# AVR-Megaboard-V1.net
KiCad netlist of a schematic drawn in EAGLE
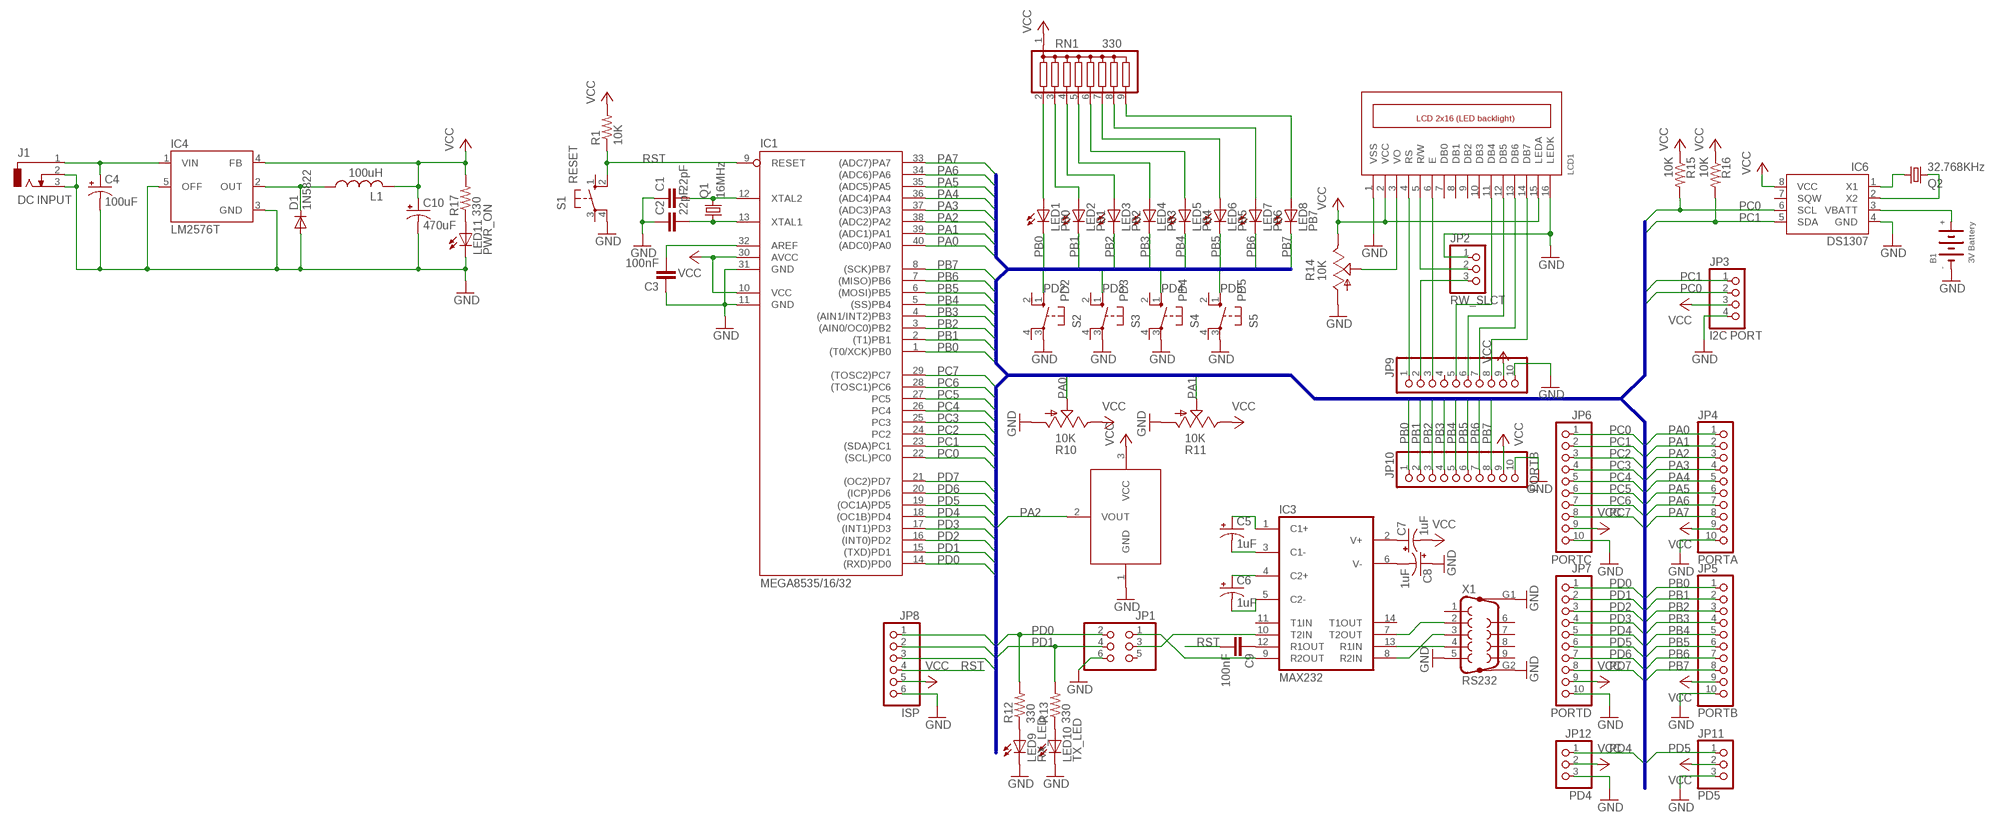
[diagram p0: schematic, sheet 1]

(export (version "E")
  (design (tool "Eeschema 10.0.6"))
  (components
    (comp (ref "B1")
      (value "3V Battery")
      (footprint "eagle-import:CR2032")
      (libsource (lib "eagle-import") (part "BATTERYCR2032"))
    )
    (comp (ref "C1")
      (value "22pF")
      (footprint "eagle-import:C025-024X044")
      (libsource (lib "eagle-import") (part "C-EU025-024X044"))
    )
    (comp (ref "C2")
      (value "22pF")
      (footprint "eagle-import:C025-024X044")
      (libsource (lib "eagle-import") (part "C-EU025-024X044"))
    )
    (comp (ref "C3")
      (value "100nF")
      (footprint "eagle-import:C025-024X044")
      (libsource (lib "eagle-import") (part "C-EU025-024X044"))
    )
    (comp (ref "C4")
      (value "100uF")
      (footprint "eagle-import:E2,5-6")
      (libsource (lib "eagle-import") (part "CPOL-USE2.5-6"))
    )
    (comp (ref "C5")
      (value "1uF")
      (footprint "eagle-import:E2-4")
      (libsource (lib "eagle-import") (part "CPOL-USE2-4"))
    )
    (comp (ref "C6")
      (value "1uF")
      (footprint "eagle-import:E2-4")
      (libsource (lib "eagle-import") (part "CPOL-USE2-4"))
    )
    (comp (ref "C7")
      (value "1uF")
      (footprint "eagle-import:E2-4")
      (libsource (lib "eagle-import") (part "CPOL-USE2-4"))
    )
    (comp (ref "C8")
      (value "1uF")
      (footprint "eagle-import:E2-4")
      (libsource (lib "eagle-import") (part "CPOL-USE2-4"))
    )
    (comp (ref "C9")
      (value "100nF")
      (footprint "eagle-import:C025-024X044")
      (libsource (lib "eagle-import") (part "C-EU025-024X044"))
    )
    (comp (ref "C10")
      (value "470uF")
      (footprint "eagle-import:E3,5-8")
      (libsource (lib "eagle-import") (part "CPOL-USE3.5-8"))
    )
    (comp (ref "D1")
      (value "1N5822")
      (footprint "eagle-import:DO201-15")
      (libsource (lib "eagle-import") (part "1N5400"))
    )
    (comp (ref "IC1")
      (value "MEGA8535/16/32")
      (footprint "eagle-import:DIL40")
      (fields (field (name "MPN") "ATMEGA8535-16PU"))
      (libsource (lib "eagle-import") (part "MEGA8535-P"))
    )
    (comp (ref "IC2")
      (value "LM35")
      (footprint "eagle-import:TO92")
      (libsource (lib "eagle-import") (part "LM35"))
    )
    (comp (ref "IC3")
      (value "MAX232")
      (footprint "eagle-import:DIL16")
      (fields (field (name "MF") "MAXIM") (field (name "MPN") "MAX232ACPE+"))
      (libsource (lib "eagle-import") (part "MAX232"))
    )
    (comp (ref "IC4")
      (value "LM2576T")
      (footprint "eagle-import:TO220-5")
      (libsource (lib "eagle-import") (part "LM2576T"))
    )
    (comp (ref "IC6")
      (value "DS1307")
      (footprint "eagle-import:DIP08")
      (libsource (lib "eagle-import") (part "DS1307"))
    )
    (comp (ref "J1")
      (value "DC INPUT")
      (footprint "eagle-import:DCJ0202")
      (libsource (lib "eagle-import") (part "DCJ0202"))
    )
    (comp (ref "JP1")
      (value "PINHD-2X3")
      (footprint "eagle-import:2X03")
      (libsource (lib "eagle-import") (part "PINHD-2X3"))
    )
    (comp (ref "JP2")
      (value "RW_SLCT")
      (footprint "eagle-import:1X03")
      (libsource (lib "eagle-import") (part "PINHD-1X3"))
    )
    (comp (ref "JP3")
      (value "I2C PORT")
      (footprint "eagle-import:1X04")
      (libsource (lib "eagle-import") (part "PINHD-1X4"))
    )
    (comp (ref "JP4")
      (value "PORTA")
      (footprint "eagle-import:1X10")
      (libsource (lib "eagle-import") (part "PINHD-1X10"))
    )
    (comp (ref "JP5")
      (value "PORTB")
      (footprint "eagle-import:1X10")
      (libsource (lib "eagle-import") (part "PINHD-1X10"))
    )
    (comp (ref "JP6")
      (value "PORTC")
      (footprint "eagle-import:1X10")
      (libsource (lib "eagle-import") (part "PINHD-1X10"))
    )
    (comp (ref "JP7")
      (value "PORTD")
      (footprint "eagle-import:1X10")
      (libsource (lib "eagle-import") (part "PINHD-1X10"))
    )
    (comp (ref "JP8")
      (value "ISP")
      (footprint "eagle-import:1X06")
      (libsource (lib "eagle-import") (part "PINHD-1X6"))
    )
    (comp (ref "JP9")
      (value "PINHD-1X10")
      (footprint "eagle-import:1X10")
      (libsource (lib "eagle-import") (part "PINHD-1X10"))
    )
    (comp (ref "JP10")
      (value "PORTB")
      (footprint "eagle-import:1X10")
      (libsource (lib "eagle-import") (part "PINHD-1X10"))
    )
    (comp (ref "JP11")
      (value "PD5")
      (footprint "eagle-import:1X03")
      (libsource (lib "eagle-import") (part "PINHD-1X3"))
    )
    (comp (ref "JP12")
      (value "PD4")
      (footprint "eagle-import:1X03")
      (libsource (lib "eagle-import") (part "PINHD-1X3"))
    )
    (comp (ref "L1")
      (value "100uH")
      (footprint "eagle-import:TJ3-U2")
      (libsource (lib "eagle-import") (part "L-USTJ3-U2"))
    )
    (comp (ref "LCD1")
      (value "LCD_2X16")
      (footprint "eagle-import:HY-1602F")
      (libsource (lib "eagle-import") (part "LCD_2X16_SIL"))
    )
    (comp (ref "LED1")
      (value "PB0")
      (footprint "eagle-import:LED3MM")
      (libsource (lib "eagle-import") (part "LED3MM"))
    )
    (comp (ref "LED2")
      (value "PB1")
      (footprint "eagle-import:LED3MM")
      (libsource (lib "eagle-import") (part "LED3MM"))
    )
    (comp (ref "LED3")
      (value "PB2")
      (footprint "eagle-import:LED3MM")
      (libsource (lib "eagle-import") (part "LED3MM"))
    )
    (comp (ref "LED4")
      (value "PB3")
      (footprint "eagle-import:LED3MM")
      (libsource (lib "eagle-import") (part "LED3MM"))
    )
    (comp (ref "LED5")
      (value "PB4")
      (footprint "eagle-import:LED3MM")
      (libsource (lib "eagle-import") (part "LED3MM"))
    )
    (comp (ref "LED6")
      (value "PB5")
      (footprint "eagle-import:LED3MM")
      (libsource (lib "eagle-import") (part "LED3MM"))
    )
    (comp (ref "LED7")
      (value "PB6")
      (footprint "eagle-import:LED3MM")
      (libsource (lib "eagle-import") (part "LED3MM"))
    )
    (comp (ref "LED8")
      (value "PB7")
      (footprint "eagle-import:LED3MM")
      (libsource (lib "eagle-import") (part "LED3MM"))
    )
    (comp (ref "LED9")
      (value "RX_LED")
      (footprint "eagle-import:LED3MM")
      (libsource (lib "eagle-import") (part "LED3MM"))
    )
    (comp (ref "LED10")
      (value "TX_LED")
      (footprint "eagle-import:LED3MM")
      (libsource (lib "eagle-import") (part "LED3MM"))
    )
    (comp (ref "LED11")
      (value "PWR_ON")
      (footprint "eagle-import:LED3MM")
      (libsource (lib "eagle-import") (part "LED3MM"))
    )
    (comp (ref "Q1")
      (value "16MHz")
      (footprint "eagle-import:HC49_S")
      (libsource (lib "eagle-import") (part "CRYSTALHC49S"))
    )
    (comp (ref "Q2")
      (value "32.768KHz")
      (footprint "eagle-import:TC26H")
      (libsource (lib "eagle-import") (part "CRYSTALTC26H"))
    )
    (comp (ref "R1")
      (value "10K")
      (footprint "eagle-import:0207_10")
      (libsource (lib "eagle-import") (part "R-US_0207/10"))
    )
    (comp (ref "R10")
      (value "10K")
      (footprint "eagle-import:CA6V")
      (libsource (lib "eagle-import") (part "TRIM_US-CA6V"))
    )
    (comp (ref "R11")
      (value "10K")
      (footprint "eagle-import:CA6V")
      (libsource (lib "eagle-import") (part "TRIM_US-CA6V"))
    )
    (comp (ref "R12")
      (value "330")
      (footprint "eagle-import:0207_5V")
      (libsource (lib "eagle-import") (part "R-US_0207/5V"))
    )
    (comp (ref "R13")
      (value "330")
      (footprint "eagle-import:0207_5V")
      (libsource (lib "eagle-import") (part "R-US_0207/5V"))
    )
    (comp (ref "R14")
      (value "10K")
      (footprint "eagle-import:CA6V")
      (libsource (lib "eagle-import") (part "TRIM_US-CA6V"))
    )
    (comp (ref "R15")
      (value "10K")
      (footprint "eagle-import:0207_10")
      (libsource (lib "eagle-import") (part "R-US_0207/10"))
    )
    (comp (ref "R16")
      (value "10K")
      (footprint "eagle-import:0207_10")
      (libsource (lib "eagle-import") (part "R-US_0207/10"))
    )
    (comp (ref "R17")
      (value "330")
      (footprint "eagle-import:0207_2V")
      (libsource (lib "eagle-import") (part "R-US_0207/2V"))
    )
    (comp (ref "RN1")
      (value "330")
      (footprint "eagle-import:SIL9")
      (libsource (lib "eagle-import") (part "G08R"))
    )
    (comp (ref "S1")
      (value "RESET")
      (footprint "eagle-import:B3F-10XX")
      (fields (field (name "MPN") "B3F-1000"))
      (libsource (lib "eagle-import") (part "10-XX"))
    )
    (comp (ref "S2")
      (value "PD2")
      (footprint "eagle-import:B3F-10XX")
      (fields (field (name "MPN") "B3F-1000"))
      (libsource (lib "eagle-import") (part "10-XX"))
    )
    (comp (ref "S3")
      (value "PD3")
      (footprint "eagle-import:B3F-10XX")
      (fields (field (name "MPN") "B3F-1000"))
      (libsource (lib "eagle-import") (part "10-XX"))
    )
    (comp (ref "S4")
      (value "PD4")
      (footprint "eagle-import:B3F-10XX")
      (fields (field (name "MPN") "B3F-1000"))
      (libsource (lib "eagle-import") (part "10-XX"))
    )
    (comp (ref "S5")
      (value "PD5")
      (footprint "eagle-import:B3F-10XX")
      (fields (field (name "MPN") "B3F-1000"))
      (libsource (lib "eagle-import") (part "10-XX"))
    )
    (comp (ref "X1")
      (value "RS232")
      (footprint "eagle-import:F09HP")
      (libsource (lib "eagle-import") (part "F09HP"))
    )
  )
  (nets
    (net (code "1") (name "/PA0") (class "Default")
      (node (ref "IC1") (pin "40") (pinfunction "(ADC0)PA0_40") (pintype "bidirectional"))
      (node (ref "JP4") (pin "1") (pinfunction "1_1") (pintype "passive"))
      (node (ref "R10") (pin "S") (pinfunction "S_S") (pintype "passive"))
    )
    (net (code "2") (name "/PA1") (class "Default")
      (node (ref "IC1") (pin "39") (pinfunction "(ADC1)PA1_39") (pintype "bidirectional"))
      (node (ref "JP4") (pin "2") (pinfunction "2_2") (pintype "passive"))
      (node (ref "R11") (pin "S") (pinfunction "S_S") (pintype "passive"))
    )
    (net (code "3") (name "/PA2") (class "Default")
      (node (ref "IC1") (pin "38") (pinfunction "(ADC2)PA2_38") (pintype "bidirectional"))
      (node (ref "IC2") (pin "2") (pinfunction "VOUT_2") (pintype "output"))
      (node (ref "JP4") (pin "3") (pinfunction "3_3") (pintype "passive"))
    )
    (net (code "4") (name "/PA3") (class "Default")
      (node (ref "IC1") (pin "37") (pinfunction "(ADC3)PA3_37") (pintype "bidirectional"))
      (node (ref "JP4") (pin "4") (pinfunction "4_4") (pintype "passive"))
    )
    (net (code "5") (name "/PA4") (class "Default")
      (node (ref "IC1") (pin "36") (pinfunction "(ADC4)PA4_36") (pintype "bidirectional"))
      (node (ref "JP4") (pin "5") (pinfunction "5_5") (pintype "passive"))
    )
    (net (code "6") (name "/PA5") (class "Default")
      (node (ref "IC1") (pin "35") (pinfunction "(ADC5)PA5_35") (pintype "bidirectional"))
      (node (ref "JP4") (pin "6") (pinfunction "6_6") (pintype "passive"))
    )
    (net (code "7") (name "/PA6") (class "Default")
      (node (ref "IC1") (pin "34") (pinfunction "(ADC6)PA6_34") (pintype "bidirectional"))
      (node (ref "JP4") (pin "7") (pinfunction "7_7") (pintype "passive"))
    )
    (net (code "8") (name "/PA7") (class "Default")
      (node (ref "IC1") (pin "33") (pinfunction "(ADC7)PA7_33") (pintype "bidirectional"))
      (node (ref "JP4") (pin "8") (pinfunction "8_8") (pintype "passive"))
    )
    (net (code "9") (name "/PB0") (class "Default")
      (node (ref "IC1") (pin "1") (pinfunction "(T0/XCK)PB0_1") (pintype "bidirectional"))
      (node (ref "JP10") (pin "1") (pinfunction "1_1") (pintype "passive"))
      (node (ref "JP5") (pin "1") (pinfunction "1_1") (pintype "passive"))
      (node (ref "LED1") (pin "K") (pinfunction "C_K") (pintype "passive"))
    )
    (net (code "10") (name "/PB1") (class "Default")
      (node (ref "IC1") (pin "2") (pinfunction "(T1)PB1_2") (pintype "bidirectional"))
      (node (ref "JP10") (pin "2") (pinfunction "2_2") (pintype "passive"))
      (node (ref "JP5") (pin "2") (pinfunction "2_2") (pintype "passive"))
      (node (ref "LED2") (pin "K") (pinfunction "C_K") (pintype "passive"))
    )
    (net (code "11") (name "/PB2") (class "Default")
      (node (ref "IC1") (pin "3") (pinfunction "(AIN0/OC0)PB2_3") (pintype "bidirectional"))
      (node (ref "JP10") (pin "3") (pinfunction "3_3") (pintype "passive"))
      (node (ref "JP5") (pin "3") (pinfunction "3_3") (pintype "passive"))
      (node (ref "LED3") (pin "K") (pinfunction "C_K") (pintype "passive"))
    )
    (net (code "12") (name "/PB3") (class "Default")
      (node (ref "IC1") (pin "4") (pinfunction "(AIN1/INT2)PB3_4") (pintype "bidirectional"))
      (node (ref "JP10") (pin "4") (pinfunction "4_4") (pintype "passive"))
      (node (ref "JP5") (pin "4") (pinfunction "4_4") (pintype "passive"))
      (node (ref "LED4") (pin "K") (pinfunction "C_K") (pintype "passive"))
    )
    (net (code "13") (name "/PB4") (class "Default")
      (node (ref "IC1") (pin "5") (pinfunction "(SS)PB4_5") (pintype "bidirectional"))
      (node (ref "JP10") (pin "5") (pinfunction "5_5") (pintype "passive"))
      (node (ref "JP5") (pin "5") (pinfunction "5_5") (pintype "passive"))
      (node (ref "LED5") (pin "K") (pinfunction "C_K") (pintype "passive"))
    )
    (net (code "14") (name "/PB5") (class "Default")
      (node (ref "IC1") (pin "6") (pinfunction "(MOSI)PB5_6") (pintype "bidirectional"))
      (node (ref "JP10") (pin "6") (pinfunction "6_6") (pintype "passive"))
      (node (ref "JP5") (pin "6") (pinfunction "6_6") (pintype "passive"))
      (node (ref "JP8") (pin "1") (pinfunction "1_1") (pintype "passive"))
      (node (ref "LED6") (pin "K") (pinfunction "C_K") (pintype "passive"))
    )
    (net (code "15") (name "/PB6") (class "Default")
      (node (ref "IC1") (pin "7") (pinfunction "(MISO)PB6_7") (pintype "bidirectional"))
      (node (ref "JP10") (pin "7") (pinfunction "7_7") (pintype "passive"))
      (node (ref "JP5") (pin "7") (pinfunction "7_7") (pintype "passive"))
      (node (ref "JP8") (pin "2") (pinfunction "2_2") (pintype "passive"))
      (node (ref "LED7") (pin "K") (pinfunction "C_K") (pintype "passive"))
    )
    (net (code "16") (name "/PB7") (class "Default")
      (node (ref "IC1") (pin "8") (pinfunction "(SCK)PB7_8") (pintype "bidirectional"))
      (node (ref "JP10") (pin "8") (pinfunction "8_8") (pintype "passive"))
      (node (ref "JP5") (pin "8") (pinfunction "8_8") (pintype "passive"))
      (node (ref "JP8") (pin "3") (pinfunction "3_3") (pintype "passive"))
      (node (ref "LED8") (pin "K") (pinfunction "C_K") (pintype "passive"))
    )
    (net (code "17") (name "/PC0") (class "Default")
      (node (ref "IC1") (pin "22") (pinfunction "(SCL)PC0_22") (pintype "bidirectional"))
      (node (ref "IC6") (pin "6") (pinfunction "SCL_6") (pintype "bidirectional"))
      (node (ref "JP3") (pin "2") (pinfunction "2_2") (pintype "passive"))
      (node (ref "JP6") (pin "1") (pinfunction "1_1") (pintype "passive"))
      (node (ref "R15") (pin "2") (pinfunction "2_2") (pintype "passive"))
    )
    (net (code "18") (name "/PC1") (class "Default")
      (node (ref "IC1") (pin "23") (pinfunction "(SDA)PC1_23") (pintype "bidirectional"))
      (node (ref "IC6") (pin "5") (pinfunction "SDA_5") (pintype "bidirectional"))
      (node (ref "JP3") (pin "1") (pinfunction "1_1") (pintype "passive"))
      (node (ref "JP6") (pin "2") (pinfunction "2_2") (pintype "passive"))
      (node (ref "R16") (pin "2") (pinfunction "2_2") (pintype "passive"))
    )
    (net (code "19") (name "/PC2") (class "Default")
      (node (ref "IC1") (pin "24") (pinfunction "PC2_24") (pintype "bidirectional"))
      (node (ref "JP6") (pin "3") (pinfunction "3_3") (pintype "passive"))
    )
    (net (code "20") (name "/PC3") (class "Default")
      (node (ref "IC1") (pin "25") (pinfunction "PC3_25") (pintype "bidirectional"))
      (node (ref "JP6") (pin "4") (pinfunction "4_4") (pintype "passive"))
    )
    (net (code "21") (name "/PC4") (class "Default")
      (node (ref "IC1") (pin "26") (pinfunction "PC4_26") (pintype "bidirectional"))
      (node (ref "JP6") (pin "5") (pinfunction "5_5") (pintype "passive"))
    )
    (net (code "22") (name "/PC5") (class "Default")
      (node (ref "IC1") (pin "27") (pinfunction "PC5_27") (pintype "bidirectional"))
      (node (ref "JP6") (pin "6") (pinfunction "6_6") (pintype "passive"))
    )
    (net (code "23") (name "/PC6") (class "Default")
      (node (ref "IC1") (pin "28") (pinfunction "(TOSC1)PC6_28") (pintype "bidirectional"))
      (node (ref "JP6") (pin "7") (pinfunction "7_7") (pintype "passive"))
    )
    (net (code "24") (name "/PC7") (class "Default")
      (node (ref "IC1") (pin "29") (pinfunction "(TOSC2)PC7_29") (pintype "bidirectional"))
      (node (ref "JP6") (pin "8") (pinfunction "8_8") (pintype "passive"))
    )
    (net (code "25") (name "/PD0") (class "Default")
      (node (ref "IC1") (pin "14") (pinfunction "(RXD)PD0_14") (pintype "bidirectional"))
      (node (ref "JP1") (pin "2") (pinfunction "2_2") (pintype "passive"))
      (node (ref "JP7") (pin "1") (pinfunction "1_1") (pintype "passive"))
      (node (ref "R12") (pin "2") (pinfunction "2_2") (pintype "passive"))
    )
    (net (code "26") (name "/PD1") (class "Default")
      (node (ref "IC1") (pin "15") (pinfunction "(TXD)PD1_15") (pintype "bidirectional"))
      (node (ref "JP1") (pin "4") (pinfunction "4_4") (pintype "passive"))
      (node (ref "JP7") (pin "2") (pinfunction "2_2") (pintype "passive"))
      (node (ref "R13") (pin "2") (pinfunction "2_2") (pintype "passive"))
    )
    (net (code "27") (name "/PD2") (class "Default")
      (node (ref "IC1") (pin "16") (pinfunction "(INT0)PD2_16") (pintype "bidirectional"))
      (node (ref "JP7") (pin "3") (pinfunction "3_3") (pintype "passive"))
      (node (ref "S2") (pin "1") (pinfunction "S_1") (pintype "passive"))
    )
    (net (code "28") (name "/PD3") (class "Default")
      (node (ref "IC1") (pin "17") (pinfunction "(INT1)PD3_17") (pintype "bidirectional"))
      (node (ref "JP7") (pin "4") (pinfunction "4_4") (pintype "passive"))
      (node (ref "S3") (pin "1") (pinfunction "S_1") (pintype "passive"))
    )
    (net (code "29") (name "/PD4") (class "Default")
      (node (ref "IC1") (pin "18") (pinfunction "(OC1B)PD4_18") (pintype "bidirectional"))
      (node (ref "JP12") (pin "1") (pinfunction "1_1") (pintype "passive"))
      (node (ref "JP7") (pin "5") (pinfunction "5_5") (pintype "passive"))
      (node (ref "S4") (pin "1") (pinfunction "S_1") (pintype "passive"))
    )
    (net (code "30") (name "/PD5") (class "Default")
      (node (ref "IC1") (pin "19") (pinfunction "(OC1A)PD5_19") (pintype "bidirectional"))
      (node (ref "JP11") (pin "1") (pinfunction "1_1") (pintype "passive"))
      (node (ref "JP7") (pin "6") (pinfunction "6_6") (pintype "passive"))
      (node (ref "S5") (pin "1") (pinfunction "S_1") (pintype "passive"))
    )
    (net (code "31") (name "/PD6") (class "Default")
      (node (ref "IC1") (pin "20") (pinfunction "(ICP)PD6_20") (pintype "bidirectional"))
      (node (ref "JP7") (pin "7") (pinfunction "7_7") (pintype "passive"))
    )
    (net (code "32") (name "/PD7") (class "Default")
      (node (ref "IC1") (pin "21") (pinfunction "(OC2)PD7_21") (pintype "bidirectional"))
      (node (ref "JP7") (pin "8") (pinfunction "8_8") (pintype "passive"))
    )
    (net (code "33") (name "/RST") (class "Default")
      (node (ref "C9") (pin "2") (pinfunction "2_2") (pintype "passive"))
      (node (ref "IC1") (pin "9") (pinfunction "RESET_9") (pintype "input"))
      (node (ref "JP8") (pin "4") (pinfunction "4_4") (pintype "passive"))
      (node (ref "R1") (pin "1") (pinfunction "1_1") (pintype "passive"))
      (node (ref "S1") (pin "2") (pinfunction "S1_2") (pintype "passive"))
    )
    (net (code "34") (name "GND") (class "Default")
      (node (ref "B1") (pin "-") (pinfunction "-_-") (pintype "passive"))
      (node (ref "C1") (pin "1") (pinfunction "1_1") (pintype "passive"))
      (node (ref "C10") (pin "-") (pinfunction "-_-") (pintype "passive"))
      (node (ref "C2") (pin "1") (pinfunction "1_1") (pintype "passive"))
      (node (ref "C3") (pin "1") (pinfunction "1_1") (pintype "passive"))
      (node (ref "C4") (pin "-") (pinfunction "-_-") (pintype "passive"))
      (node (ref "C8") (pin "+") (pinfunction "+_+") (pintype "passive"))
      (node (ref "D1") (pin "A") (pinfunction "A_A") (pintype "passive"))
      (node (ref "IC1") (pin "11") (pinfunction "GND_11") (pintype "power_in"))
      (node (ref "IC1") (pin "31") (pinfunction "GND_31") (pintype "power_in"))
      (node (ref "IC2") (pin "1") (pinfunction "GND_1") (pintype "power_in"))
      (node (ref "IC4") (pin "3") (pinfunction "GND_3") (pintype "power_in"))
      (node (ref "IC4") (pin "5") (pinfunction "OFF_5") (pintype "input"))
      (node (ref "IC6") (pin "4") (pinfunction "GND_4") (pintype "bidirectional"))
      (node (ref "J1") (pin "2") (pinfunction "2_2") (pintype "passive"))
      (node (ref "J1") (pin "3") (pinfunction "3_3") (pintype "passive"))
      (node (ref "JP1") (pin "6") (pinfunction "6_6") (pintype "passive"))
      (node (ref "JP10") (pin "10") (pinfunction "10_10") (pintype "passive"))
      (node (ref "JP11") (pin "3") (pinfunction "3_3") (pintype "passive"))
      (node (ref "JP12") (pin "3") (pinfunction "3_3") (pintype "passive"))
      (node (ref "JP2") (pin "1") (pinfunction "1_1") (pintype "passive"))
      (node (ref "JP3") (pin "4") (pinfunction "4_4") (pintype "passive"))
      (node (ref "JP4") (pin "10") (pinfunction "10_10") (pintype "passive"))
      (node (ref "JP5") (pin "10") (pinfunction "10_10") (pintype "passive"))
      (node (ref "JP6") (pin "10") (pinfunction "10_10") (pintype "passive"))
      (node (ref "JP7") (pin "10") (pinfunction "10_10") (pintype "passive"))
      (node (ref "JP8") (pin "6") (pinfunction "6_6") (pintype "passive"))
      (node (ref "JP9") (pin "10") (pinfunction "10_10") (pintype "passive"))
      (node (ref "LCD1") (pin "1") (pinfunction "VSS_1") (pintype "power_in"))
      (node (ref "LCD1") (pin "16") (pinfunction "LEDK_16") (pintype "passive"))
      (node (ref "LED10") (pin "K") (pinfunction "C_K") (pintype "passive"))
      (node (ref "LED11") (pin "K") (pinfunction "C_K") (pintype "passive"))
      (node (ref "LED9") (pin "K") (pinfunction "C_K") (pintype "passive"))
      (node (ref "R10") (pin "A") (pinfunction "A_A") (pintype "passive"))
      (node (ref "R11") (pin "A") (pinfunction "A_A") (pintype "passive"))
      (node (ref "R14") (pin "A") (pinfunction "A_A") (pintype "passive"))
      (node (ref "S1") (pin "4") (pinfunction "P1_4") (pintype "passive"))
      (node (ref "S2") (pin "3") (pinfunction "P_3") (pintype "passive"))
      (node (ref "S3") (pin "3") (pinfunction "P_3") (pintype "passive"))
      (node (ref "S4") (pin "3") (pinfunction "P_3") (pintype "passive"))
      (node (ref "S5") (pin "3") (pinfunction "P_3") (pintype "passive"))
      (node (ref "X1") (pin "5") (pinfunction "5_5") (pintype "passive"))
      (node (ref "X1") (pin "G1") (pinfunction "G1_G1") (pintype "passive"))
      (node (ref "X1") (pin "G2") (pinfunction "G2_G2") (pintype "passive"))
    )
    (net (code "35") (name "Net-(IC1-AREF)") (class "Default")
      (node (ref "C3") (pin "2") (pinfunction "2_2") (pintype "passive"))
      (node (ref "IC1") (pin "32") (pinfunction "AREF_32") (pintype "passive"))
    )
    (net (code "36") (name "Net-(IC1-XTAL1)") (class "Default")
      (node (ref "C2") (pin "2") (pinfunction "2_2") (pintype "passive"))
      (node (ref "IC1") (pin "13") (pinfunction "XTAL1_13") (pintype "bidirectional"))
      (node (ref "Q1") (pin "1") (pinfunction "1_1") (pintype "passive"))
    )
    (net (code "37") (name "Net-(IC1-XTAL2)") (class "Default")
      (node (ref "C1") (pin "2") (pinfunction "2_2") (pintype "passive"))
      (node (ref "IC1") (pin "12") (pinfunction "XTAL2_12") (pintype "bidirectional"))
      (node (ref "Q1") (pin "2") (pinfunction "2_2") (pintype "passive"))
    )
    (net (code "38") (name "Net-(IC3A-C1+)") (class "Default")
      (node (ref "C5") (pin "+") (pinfunction "+_+") (pintype "passive"))
      (node (ref "IC3") (pin "1") (pinfunction "C1+_1") (pintype "bidirectional"))
    )
    (net (code "39") (name "Net-(IC3A-C1-)") (class "Default")
      (node (ref "C5") (pin "-") (pinfunction "-_-") (pintype "passive"))
      (node (ref "IC3") (pin "3") (pinfunction "C1-_3") (pintype "bidirectional"))
    )
    (net (code "40") (name "Net-(IC3A-C2+)") (class "Default")
      (node (ref "C6") (pin "+") (pinfunction "+_+") (pintype "passive"))
      (node (ref "IC3") (pin "4") (pinfunction "C2+_4") (pintype "bidirectional"))
    )
    (net (code "41") (name "Net-(IC3A-C2-)") (class "Default")
      (node (ref "C6") (pin "-") (pinfunction "-_-") (pintype "passive"))
      (node (ref "IC3") (pin "5") (pinfunction "C2-_5") (pintype "bidirectional"))
    )
    (net (code "42") (name "Net-(IC3A-R1IN)") (class "Default")
      (node (ref "IC3") (pin "13") (pinfunction "R1IN_13") (pintype "input"))
      (node (ref "X1") (pin "4") (pinfunction "4_4") (pintype "passive"))
    )
    (net (code "43") (name "Net-(IC3A-R1OUT)") (class "Default")
      (node (ref "C9") (pin "1") (pinfunction "1_1") (pintype "passive"))
      (node (ref "IC3") (pin "12") (pinfunction "R1OUT_12") (pintype "output"))
    )
    (net (code "44") (name "Net-(IC3A-R2IN)") (class "Default")
      (node (ref "IC3") (pin "8") (pinfunction "R2IN_8") (pintype "input"))
      (node (ref "X1") (pin "3") (pinfunction "3_3") (pintype "passive"))
    )
    (net (code "45") (name "Net-(IC3A-R2OUT)") (class "Default")
      (node (ref "IC3") (pin "9") (pinfunction "R2OUT_9") (pintype "output"))
      (node (ref "JP1") (pin "1") (pinfunction "1_1") (pintype "passive"))
    )
    (net (code "46") (name "Net-(IC3A-T2IN)") (class "Default")
      (node (ref "IC3") (pin "10") (pinfunction "T2IN_10") (pintype "input"))
      (node (ref "JP1") (pin "3") (pinfunction "3_3") (pintype "passive"))
    )
    (net (code "47") (name "Net-(IC3A-T2OUT)") (class "Default")
      (node (ref "IC3") (pin "7") (pinfunction "T2OUT_7") (pintype "output"))
      (node (ref "X1") (pin "2") (pinfunction "2_2") (pintype "passive"))
    )
    (net (code "48") (name "Net-(IC3A-V+)") (class "Default")
      (node (ref "C7") (pin "+") (pinfunction "+_+") (pintype "passive"))
      (node (ref "IC3") (pin "2") (pinfunction "V+_2") (pintype "bidirectional"))
    )
    (net (code "49") (name "Net-(IC3A-V-)") (class "Default")
      (node (ref "C8") (pin "-") (pinfunction "-_-") (pintype "passive"))
      (node (ref "IC3") (pin "6") (pinfunction "V-_6") (pintype "bidirectional"))
    )
    (net (code "50") (name "Net-(IC4-OUT)") (class "Default")
      (node (ref "D1") (pin "C") (pinfunction "C_C") (pintype "passive"))
      (node (ref "IC4") (pin "2") (pinfunction "OUT_2") (pintype "output"))
      (node (ref "L1") (pin "1") (pinfunction "1_1") (pintype "passive"))
    )
    (net (code "51") (name "Net-(IC4-VIN)") (class "Default")
      (node (ref "C4") (pin "+") (pinfunction "+_+") (pintype "passive"))
      (node (ref "IC4") (pin "1") (pinfunction "VIN_1") (pintype "power_in"))
      (node (ref "J1") (pin "1") (pinfunction "1_1") (pintype "passive"))
    )
    (net (code "52") (name "Net-(IC6-VBATT)") (class "Default")
      (node (ref "B1") (pin "+") (pinfunction "+_+") (pintype "passive"))
      (node (ref "IC6") (pin "3") (pinfunction "VBATT_3") (pintype "bidirectional"))
    )
    (net (code "53") (name "Net-(IC6-X1)") (class "Default")
      (node (ref "IC6") (pin "1") (pinfunction "X1_1") (pintype "bidirectional"))
      (node (ref "Q2") (pin "1") (pinfunction "1_1") (pintype "passive"))
    )
    (net (code "54") (name "Net-(IC6-X2)") (class "Default")
      (node (ref "IC6") (pin "2") (pinfunction "X2_2") (pintype "bidirectional"))
      (node (ref "Q2") (pin "2") (pinfunction "2_2") (pintype "passive"))
    )
    (net (code "55") (name "Net-(JP2-Pad3)") (class "Default")
      (node (ref "JP2") (pin "3") (pinfunction "3_3") (pintype "passive"))
      (node (ref "JP9") (pin "2") (pinfunction "2_2") (pintype "passive"))
    )
    (net (code "56") (name "Net-(LCD1-DB4)") (class "Default")
      (node (ref "JP9") (pin "5") (pinfunction "5_5") (pintype "passive"))
      (node (ref "LCD1") (pin "11") (pinfunction "DB4_11") (pintype "bidirectional"))
    )
    (net (code "57") (name "Net-(LCD1-DB5)") (class "Default")
      (node (ref "JP9") (pin "6") (pinfunction "6_6") (pintype "passive"))
      (node (ref "LCD1") (pin "12") (pinfunction "DB5_12") (pintype "bidirectional"))
    )
    (net (code "58") (name "Net-(LCD1-DB6)") (class "Default")
      (node (ref "JP9") (pin "7") (pinfunction "7_7") (pintype "passive"))
      (node (ref "LCD1") (pin "13") (pinfunction "DB6_13") (pintype "bidirectional"))
    )
    (net (code "59") (name "Net-(LCD1-DB7)") (class "Default")
      (node (ref "JP9") (pin "8") (pinfunction "8_8") (pintype "passive"))
      (node (ref "LCD1") (pin "14") (pinfunction "DB7_14") (pintype "bidirectional"))
    )
    (net (code "60") (name "Net-(LCD1-E)") (class "Default")
      (node (ref "JP9") (pin "3") (pinfunction "3_3") (pintype "passive"))
      (node (ref "LCD1") (pin "6") (pinfunction "E_6") (pintype "input"))
    )
    (net (code "61") (name "Net-(LCD1-RS)") (class "Default")
      (node (ref "JP9") (pin "1") (pinfunction "1_1") (pintype "passive"))
      (node (ref "LCD1") (pin "4") (pinfunction "RS_4") (pintype "input"))
    )
    (net (code "62") (name "Net-(LCD1-R{slash}W)") (class "Default")
      (node (ref "JP2") (pin "2") (pinfunction "2_2") (pintype "passive"))
      (node (ref "LCD1") (pin "5") (pinfunction "R/W_5") (pintype "input"))
    )
    (net (code "63") (name "Net-(LCD1-VO)") (class "Default")
      (node (ref "LCD1") (pin "3") (pinfunction "VO_3") (pintype "input"))
      (node (ref "R14") (pin "S") (pinfunction "S_S") (pintype "passive"))
    )
    (net (code "64") (name "Net-(LED1-PadA)") (class "Default")
      (node (ref "LED1") (pin "A") (pinfunction "A_A") (pintype "passive"))
      (node (ref "RN1") (pin "2") (pinfunction "2_2") (pintype "passive"))
    )
    (net (code "65") (name "Net-(LED2-PadA)") (class "Default")
      (node (ref "LED2") (pin "A") (pinfunction "A_A") (pintype "passive"))
      (node (ref "RN1") (pin "3") (pinfunction "3_3") (pintype "passive"))
    )
    (net (code "66") (name "Net-(LED3-PadA)") (class "Default")
      (node (ref "LED3") (pin "A") (pinfunction "A_A") (pintype "passive"))
      (node (ref "RN1") (pin "4") (pinfunction "4_4") (pintype "passive"))
    )
    (net (code "67") (name "Net-(LED4-PadA)") (class "Default")
      (node (ref "LED4") (pin "A") (pinfunction "A_A") (pintype "passive"))
      (node (ref "RN1") (pin "5") (pinfunction "5_5") (pintype "passive"))
    )
    (net (code "68") (name "Net-(LED5-PadA)") (class "Default")
      (node (ref "LED5") (pin "A") (pinfunction "A_A") (pintype "passive"))
      (node (ref "RN1") (pin "6") (pinfunction "6_6") (pintype "passive"))
    )
    (net (code "69") (name "Net-(LED6-PadA)") (class "Default")
      (node (ref "LED6") (pin "A") (pinfunction "A_A") (pintype "passive"))
      (node (ref "RN1") (pin "7") (pinfunction "7_7") (pintype "passive"))
    )
    (net (code "70") (name "Net-(LED7-PadA)") (class "Default")
      (node (ref "LED7") (pin "A") (pinfunction "A_A") (pintype "passive"))
      (node (ref "RN1") (pin "8") (pinfunction "8_8") (pintype "passive"))
    )
    (net (code "71") (name "Net-(LED8-PadA)") (class "Default")
      (node (ref "LED8") (pin "A") (pinfunction "A_A") (pintype "passive"))
      (node (ref "RN1") (pin "9") (pinfunction "9_9") (pintype "passive"))
    )
    (net (code "72") (name "Net-(LED9-PadA)") (class "Default")
      (node (ref "LED9") (pin "A") (pinfunction "A_A") (pintype "passive"))
      (node (ref "R12") (pin "1") (pinfunction "1_1") (pintype "passive"))
    )
    (net (code "73") (name "Net-(LED10-PadA)") (class "Default")
      (node (ref "LED10") (pin "A") (pinfunction "A_A") (pintype "passive"))
      (node (ref "R13") (pin "1") (pinfunction "1_1") (pintype "passive"))
    )
    (net (code "74") (name "Net-(LED11-PadA)") (class "Default")
      (node (ref "LED11") (pin "A") (pinfunction "A_A") (pintype "passive"))
      (node (ref "R17") (pin "1") (pinfunction "1_1") (pintype "passive"))
    )
    (net (code "75") (name "VCC") (class "Default")
      (node (ref "C10") (pin "+") (pinfunction "+_+") (pintype "passive"))
      (node (ref "C7") (pin "-") (pinfunction "-_-") (pintype "passive"))
      (node (ref "IC1") (pin "10") (pinfunction "VCC_10") (pintype "power_in"))
      (node (ref "IC1") (pin "30") (pinfunction "AVCC_30") (pintype "power_in"))
      (node (ref "IC2") (pin "3") (pinfunction "VCC_3") (pintype "power_in"))
      (node (ref "IC4") (pin "4") (pinfunction "FB_4") (pintype "input"))
      (node (ref "IC6") (pin "8") (pinfunction "VCC_8") (pintype "bidirectional"))
      (node (ref "JP10") (pin "9") (pinfunction "9_9") (pintype "passive"))
      (node (ref "JP11") (pin "2") (pinfunction "2_2") (pintype "passive"))
      (node (ref "JP12") (pin "2") (pinfunction "2_2") (pintype "passive"))
      (node (ref "JP3") (pin "3") (pinfunction "3_3") (pintype "passive"))
      (node (ref "JP4") (pin "9") (pinfunction "9_9") (pintype "passive"))
      (node (ref "JP5") (pin "9") (pinfunction "9_9") (pintype "passive"))
      (node (ref "JP6") (pin "9") (pinfunction "9_9") (pintype "passive"))
      (node (ref "JP7") (pin "9") (pinfunction "9_9") (pintype "passive"))
      (node (ref "JP8") (pin "5") (pinfunction "5_5") (pintype "passive"))
      (node (ref "JP9") (pin "9") (pinfunction "9_9") (pintype "passive"))
      (node (ref "L1") (pin "2") (pinfunction "2_2") (pintype "passive"))
      (node (ref "LCD1") (pin "15") (pinfunction "LEDA_15") (pintype "passive"))
      (node (ref "LCD1") (pin "2") (pinfunction "VCC_2") (pintype "power_in"))
      (node (ref "R1") (pin "2") (pinfunction "2_2") (pintype "passive"))
      (node (ref "R10") (pin "E") (pinfunction "E_E") (pintype "passive"))
      (node (ref "R11") (pin "E") (pinfunction "E_E") (pintype "passive"))
      (node (ref "R14") (pin "E") (pinfunction "E_E") (pintype "passive"))
      (node (ref "R15") (pin "1") (pinfunction "1_1") (pintype "passive"))
      (node (ref "R16") (pin "1") (pinfunction "1_1") (pintype "passive"))
      (node (ref "R17") (pin "2") (pinfunction "2_2") (pintype "passive"))
      (node (ref "RN1") (pin "1") (pinfunction "1_1") (pintype "passive"))
    )
    (net (code "76") (name "unconnected-(IC3A-T1IN-Pad11)") (class "Default")
      (node (ref "IC3") (pin "11") (pinfunction "T1IN_11") (pintype "input"))
    )
    (net (code "77") (name "unconnected-(IC3A-T1OUT-Pad14)") (class "Default")
      (node (ref "IC3") (pin "14") (pinfunction "T1OUT_14") (pintype "output"))
    )
    (net (code "78") (name "unconnected-(IC6-SQW-Pad7)") (class "Default")
      (node (ref "IC6") (pin "7") (pinfunction "SQW_7") (pintype "bidirectional"))
    )
    (net (code "79") (name "unconnected-(JP1-Pad5)") (class "Default")
      (node (ref "JP1") (pin "5") (pinfunction "5_5") (pintype "passive"))
    )
    (net (code "80") (name "unconnected-(JP9-Pad4)") (class "Default")
      (node (ref "JP9") (pin "4") (pinfunction "4_4") (pintype "passive"))
    )
    (net (code "81") (name "unconnected-(LCD1-DB0-Pad7)") (class "Default")
      (node (ref "LCD1") (pin "7") (pinfunction "DB0_7") (pintype "bidirectional"))
    )
    (net (code "82") (name "unconnected-(LCD1-DB1-Pad8)") (class "Default")
      (node (ref "LCD1") (pin "8") (pinfunction "DB1_8") (pintype "bidirectional"))
    )
    (net (code "83") (name "unconnected-(LCD1-DB2-Pad9)") (class "Default")
      (node (ref "LCD1") (pin "9") (pinfunction "DB2_9") (pintype "bidirectional"))
    )
    (net (code "84") (name "unconnected-(LCD1-DB3-Pad10)") (class "Default")
      (node (ref "LCD1") (pin "10") (pinfunction "DB3_10") (pintype "bidirectional"))
    )
    (net (code "85") (name "unconnected-(S1-P-Pad3)") (class "Default")
      (node (ref "S1") (pin "3") (pinfunction "P_3") (pintype "passive"))
    )
    (net (code "86") (name "unconnected-(S1-S-Pad1)") (class "Default")
      (node (ref "S1") (pin "1") (pinfunction "S_1") (pintype "passive"))
    )
    (net (code "87") (name "unconnected-(S2-P1-Pad4)") (class "Default")
      (node (ref "S2") (pin "4") (pinfunction "P1_4") (pintype "passive"))
    )
    (net (code "88") (name "unconnected-(S2-S1-Pad2)") (class "Default")
      (node (ref "S2") (pin "2") (pinfunction "S1_2") (pintype "passive"))
    )
    (net (code "89") (name "unconnected-(S3-P1-Pad4)") (class "Default")
      (node (ref "S3") (pin "4") (pinfunction "P1_4") (pintype "passive"))
    )
    (net (code "90") (name "unconnected-(S3-S1-Pad2)") (class "Default")
      (node (ref "S3") (pin "2") (pinfunction "S1_2") (pintype "passive"))
    )
    (net (code "91") (name "unconnected-(S4-P1-Pad4)") (class "Default")
      (node (ref "S4") (pin "4") (pinfunction "P1_4") (pintype "passive"))
    )
    (net (code "92") (name "unconnected-(S4-S1-Pad2)") (class "Default")
      (node (ref "S4") (pin "2") (pinfunction "S1_2") (pintype "passive"))
    )
    (net (code "93") (name "unconnected-(S5-P1-Pad4)") (class "Default")
      (node (ref "S5") (pin "4") (pinfunction "P1_4") (pintype "passive"))
    )
    (net (code "94") (name "unconnected-(S5-S1-Pad2)") (class "Default")
      (node (ref "S5") (pin "2") (pinfunction "S1_2") (pintype "passive"))
    )
    (net (code "95") (name "unconnected-(X1-Pad1)") (class "Default")
      (node (ref "X1") (pin "1") (pinfunction "1_1") (pintype "passive"))
    )
    (net (code "96") (name "unconnected-(X1-Pad6)") (class "Default")
      (node (ref "X1") (pin "6") (pinfunction "6_6") (pintype "passive"))
    )
    (net (code "97") (name "unconnected-(X1-Pad7)") (class "Default")
      (node (ref "X1") (pin "7") (pinfunction "7_7") (pintype "passive"))
    )
    (net (code "98") (name "unconnected-(X1-Pad8)") (class "Default")
      (node (ref "X1") (pin "8") (pinfunction "8_8") (pintype "passive"))
    )
    (net (code "99") (name "unconnected-(X1-Pad9)") (class "Default")
      (node (ref "X1") (pin "9") (pinfunction "9_9") (pintype "passive"))
    )
  )
)
